# supply.net
KiCad netlist of a schematic drawn in EAGLE
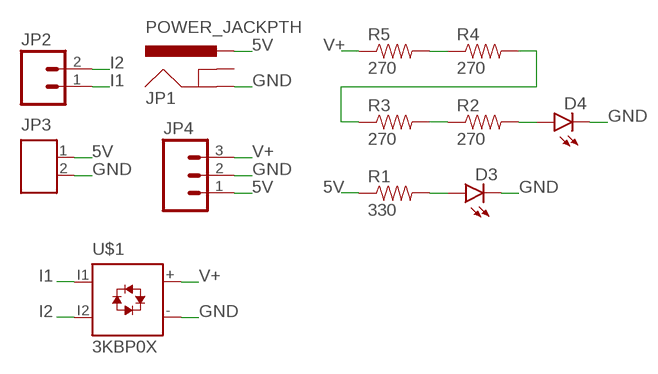
[diagram p0: schematic, sheet 1]

(export (version "E")
  (design (tool "Eeschema 10.0.6"))
  (components
    (comp (ref "D3")
      (value "LED10MM")
      (footprint "eagle-import:LED10MM")
      (libsource (lib "eagle-import") (part "LED10MM"))
    )
    (comp (ref "D4")
      (value "LED10MM")
      (footprint "eagle-import:LED10MM")
      (libsource (lib "eagle-import") (part "LED10MM"))
    )
    (comp (ref "JP1")
      (value "POWER_JACKPTH")
      (footprint "eagle-import:POWER_JACK_PTH")
      (libsource (lib "eagle-import") (part "POWER_JACKPTH"))
    )
    (comp (ref "JP2")
      (value "M025MM")
      (footprint "eagle-import:SCREWTERMINAL-5MM-2")
      (libsource (lib "eagle-import") (part "M025MM"))
    )
    (comp (ref "JP3")
      (value "M02")
      (footprint "eagle-import:JST-2-PTH")
      (libsource (lib "eagle-import") (part "M02"))
    )
    (comp (ref "JP4")
      (value "M03LONGPADS")
      (footprint "eagle-import:1X03_LONGPADS")
      (libsource (lib "eagle-import") (part "M03LONGPADS"))
    )
    (comp (ref "R1")
      (value "330")
      (footprint "eagle-import:AXIAL-0.3EZ")
      (libsource (lib "eagle-import") (part "1KOHM-1/4W-5%(PTH)HORIZ-KIT"))
    )
    (comp (ref "R2")
      (value "270")
      (footprint "eagle-import:AXIAL-0.3EZ")
      (libsource (lib "eagle-import") (part "1KOHM-1/4W-5%(PTH)HORIZ-KIT"))
    )
    (comp (ref "R3")
      (value "270")
      (footprint "eagle-import:AXIAL-0.3EZ")
      (libsource (lib "eagle-import") (part "1KOHM-1/4W-5%(PTH)HORIZ-KIT"))
    )
    (comp (ref "R4")
      (value "270")
      (footprint "eagle-import:AXIAL-0.3EZ")
      (libsource (lib "eagle-import") (part "1KOHM-1/4W-5%(PTH)HORIZ-KIT"))
    )
    (comp (ref "R5")
      (value "270")
      (footprint "eagle-import:AXIAL-0.3EZ")
      (libsource (lib "eagle-import") (part "1KOHM-1/4W-5%(PTH)HORIZ-KIT"))
    )
    (comp (ref "U$1")
      (value "3KBP0X")
      (footprint "eagle-import:3KBP0X")
      (libsource (lib "eagle-import") (part "3KBP0X"))
    )
  )
  (nets
    (net (code "1") (name "/5V") (class "Default")
      (node (ref "JP1") (pin "PWR") (pinfunction "PWR_PWR") (pintype "bidirectional"))
      (node (ref "JP3") (pin "1") (pinfunction "P$1_1") (pintype "bidirectional"))
      (node (ref "JP4") (pin "1") (pinfunction "1_1") (pintype "passive"))
      (node (ref "R1") (pin "P$1") (pinfunction "1_P$1") (pintype "passive"))
    )
    (net (code "2") (name "/GND") (class "Default")
      (node (ref "D3") (pin "C") (pinfunction "C_C") (pintype "passive"))
      (node (ref "D4") (pin "C") (pinfunction "C_C") (pintype "passive"))
      (node (ref "JP1") (pin "GND") (pinfunction "GND_GND") (pintype "bidirectional"))
      (node (ref "JP3") (pin "2") (pinfunction "P$2_2") (pintype "bidirectional"))
      (node (ref "JP4") (pin "2") (pinfunction "2_2") (pintype "passive"))
      (node (ref "U$1") (pin "-") (pinfunction "-_-") (pintype "bidirectional"))
    )
    (net (code "3") (name "/I1") (class "Default")
      (node (ref "JP2") (pin "1") (pinfunction "1_1") (pintype "passive"))
      (node (ref "U$1") (pin "I1") (pinfunction "I1_I1") (pintype "bidirectional"))
    )
    (net (code "4") (name "/I2") (class "Default")
      (node (ref "JP2") (pin "2") (pinfunction "2_2") (pintype "passive"))
      (node (ref "U$1") (pin "I2") (pinfunction "I2_I2") (pintype "bidirectional"))
    )
    (net (code "5") (name "/V+") (class "Default")
      (node (ref "JP4") (pin "3") (pinfunction "3_3") (pintype "passive"))
      (node (ref "R5") (pin "P$1") (pinfunction "1_P$1") (pintype "passive"))
      (node (ref "U$1") (pin "+") (pinfunction "+_+") (pintype "bidirectional"))
    )
    (net (code "6") (name "Net-(R1-2)") (class "Default")
      (node (ref "D3") (pin "A") (pinfunction "A_A") (pintype "passive"))
      (node (ref "R1") (pin "P$2") (pinfunction "2_P$2") (pintype "passive"))
    )
    (net (code "7") (name "Net-(R2-1)") (class "Default")
      (node (ref "R2") (pin "P$1") (pinfunction "1_P$1") (pintype "passive"))
      (node (ref "R3") (pin "P$2") (pinfunction "2_P$2") (pintype "passive"))
    )
    (net (code "8") (name "Net-(R2-2)") (class "Default")
      (node (ref "D4") (pin "A") (pinfunction "A_A") (pintype "passive"))
      (node (ref "R2") (pin "P$2") (pinfunction "2_P$2") (pintype "passive"))
    )
    (net (code "9") (name "Net-(R3-1)") (class "Default")
      (node (ref "R3") (pin "P$1") (pinfunction "1_P$1") (pintype "passive"))
      (node (ref "R4") (pin "P$2") (pinfunction "2_P$2") (pintype "passive"))
    )
    (net (code "10") (name "Net-(R4-1)") (class "Default")
      (node (ref "R4") (pin "P$1") (pinfunction "1_P$1") (pintype "passive"))
      (node (ref "R5") (pin "P$2") (pinfunction "2_P$2") (pintype "passive"))
    )
    (net (code "11") (name "unconnected-(JP1-PadGNDBREAK)") (class "Default")
      (node (ref "JP1") (pin "GNDBREAK") (pinfunction "GNDBREAK_GNDBREAK") (pintype "bidirectional"))
    )
  )
)
